# Drone_Basic.net
KiCad netlist of a schematic drawn in EAGLE
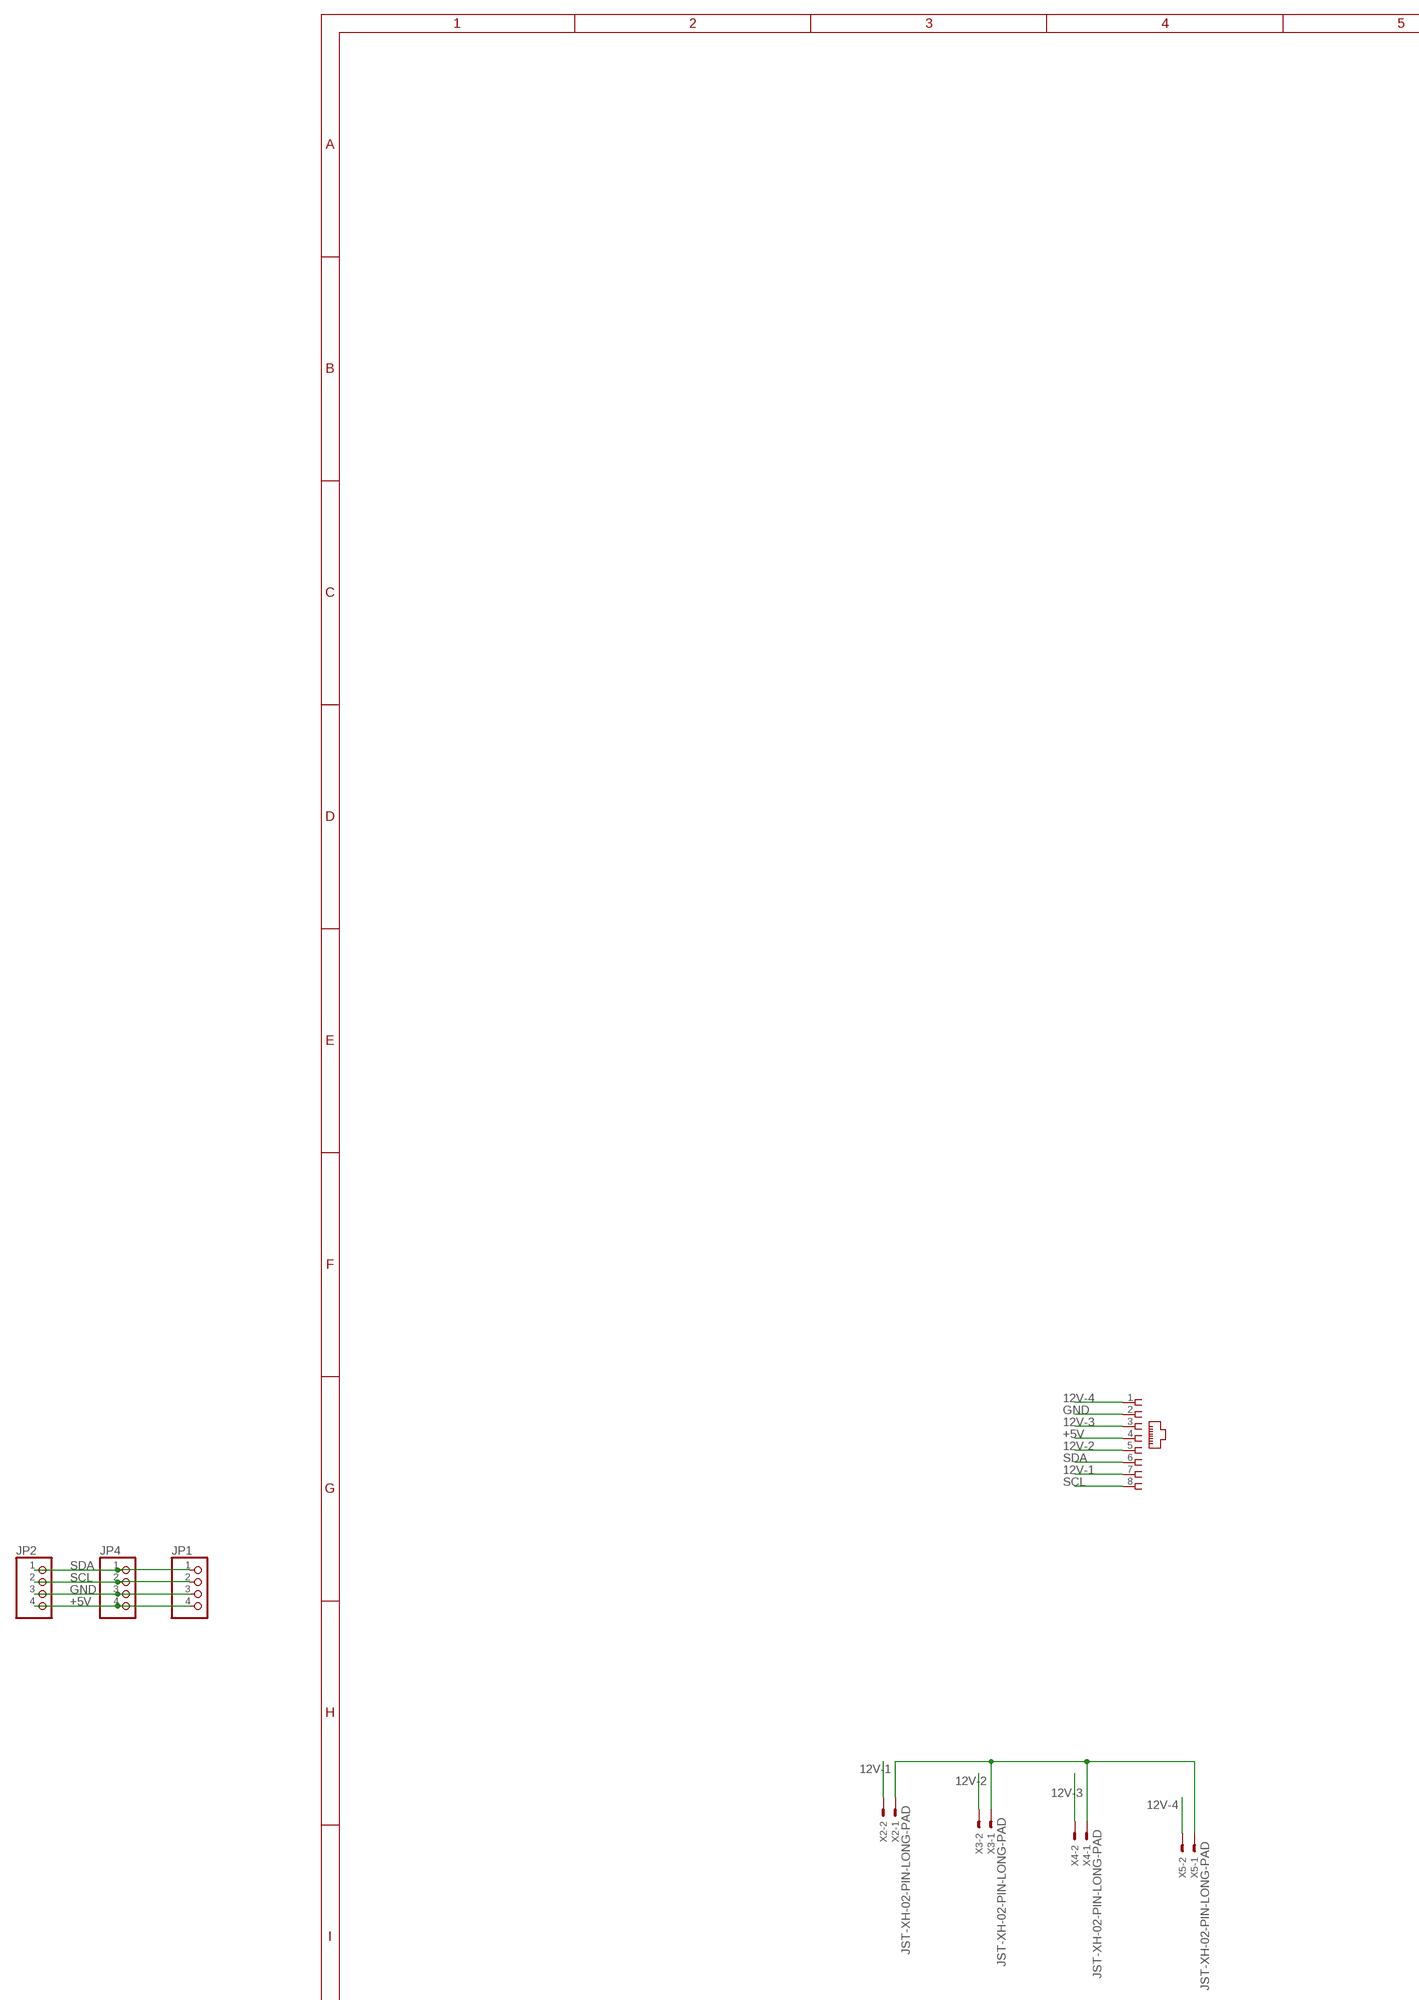
[diagram p0: schematic, sheet 1, part 1 of 2]
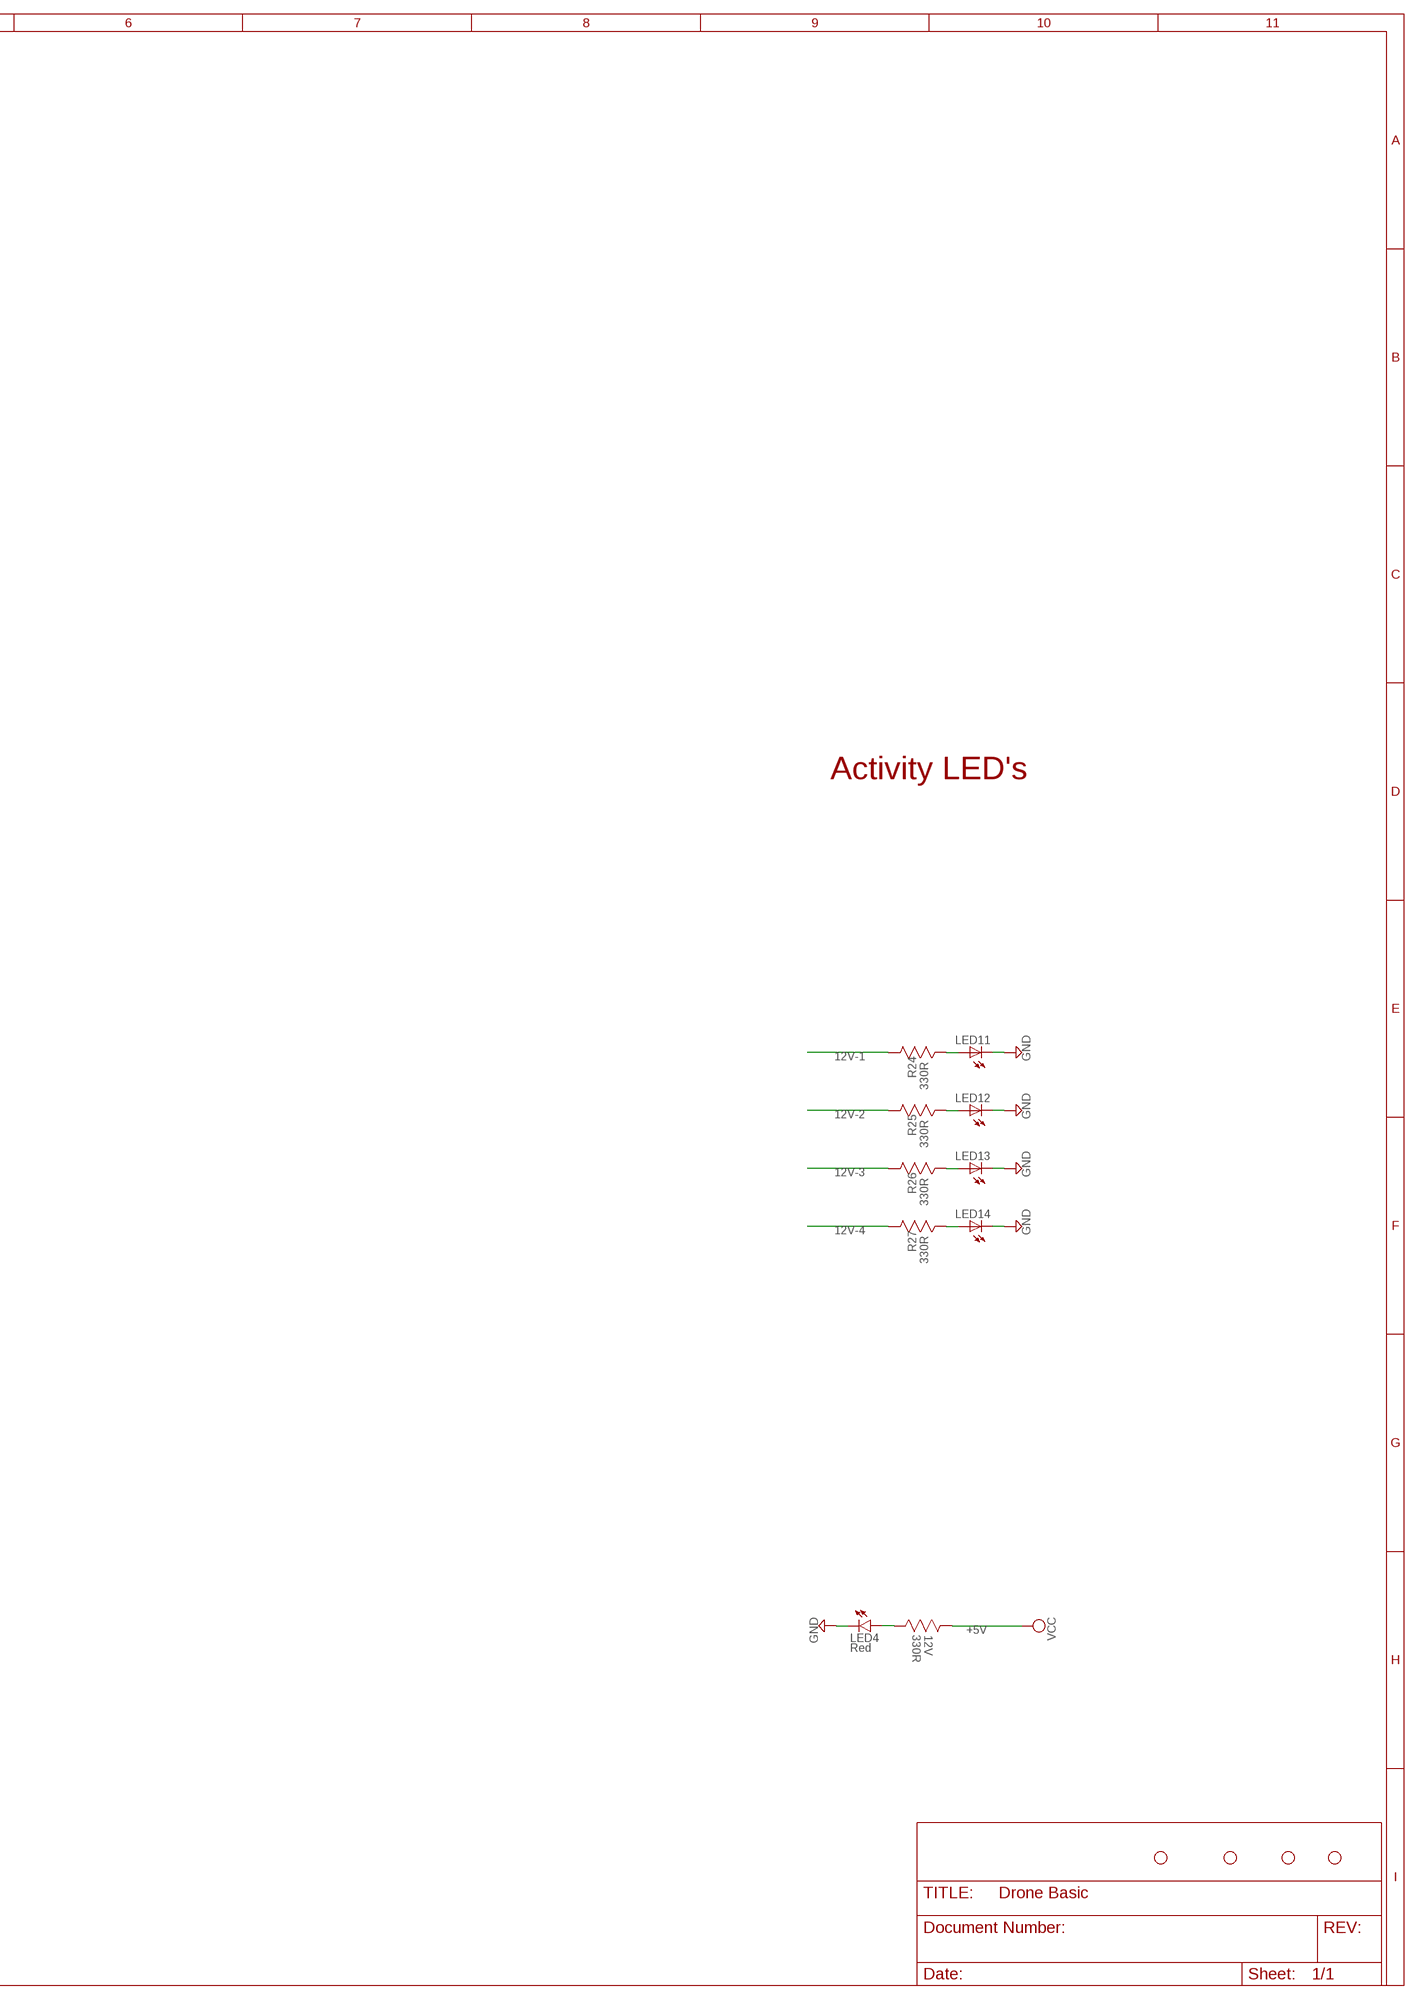
[diagram p1: schematic, sheet 1, part 2 of 2]

(export (version "E")
  (design (tool "Eeschema 10.0.6"))
  (components
    (comp (ref "12V")
      (value "330R")
      (footprint "eagle-import:RESC1608X60N")
      (fields (field (name "MPN") "MC0.063W06031%330R") (field (name "TOLERANCE") "±1%"))
      (libsource (lib "eagle-import") (part "MC0.063W06031%330R"))
    )
    (comp (ref "H5")
      (value "STAND-OFF")
      (footprint "eagle-import:STAND-OFF")
      (libsource (lib "eagle-import") (part "STAND-OFF"))
    )
    (comp (ref "H6")
      (value "STAND-OFF")
      (footprint "eagle-import:STAND-OFF")
      (libsource (lib "eagle-import") (part "STAND-OFF"))
    )
    (comp (ref "H7")
      (value "STAND-OFF")
      (footprint "eagle-import:STAND-OFF")
      (libsource (lib "eagle-import") (part "STAND-OFF"))
    )
    (comp (ref "H8")
      (value "STAND-OFF")
      (footprint "eagle-import:STAND-OFF")
      (libsource (lib "eagle-import") (part "STAND-OFF"))
    )
    (comp (ref "JP1")
      (value "PINHD-1X4")
      (footprint "eagle-import:1X04")
      (libsource (lib "eagle-import") (part "PINHD-1X4"))
    )
    (comp (ref "JP2")
      (value "PINHD-1X4")
      (footprint "eagle-import:1X04")
      (libsource (lib "eagle-import") (part "PINHD-1X4"))
    )
    (comp (ref "JP4")
      (value "PINHD-1X4")
      (footprint "eagle-import:1X04")
      (libsource (lib "eagle-import") (part "PINHD-1X4"))
    )
    (comp (ref "LED4")
      (value "Red")
      (footprint "eagle-import:LED-0603")
      (libsource (lib "eagle-import") (part "LED-RED-0603-WE"))
    )
    (comp (ref "LED11")
      (value "BLUE")
      (footprint "eagle-import:CHIPLED_0805")
      (libsource (lib "eagle-import") (part "LEDCHIPLED_0805"))
    )
    (comp (ref "LED12")
      (value "GREEN")
      (footprint "eagle-import:CHIPLED_0805")
      (libsource (lib "eagle-import") (part "LEDCHIPLED_0805"))
    )
    (comp (ref "LED13")
      (value "Yellow")
      (footprint "eagle-import:CHIPLED_0805")
      (libsource (lib "eagle-import") (part "LEDCHIPLED_0805"))
    )
    (comp (ref "LED14")
      (value "RED")
      (footprint "eagle-import:CHIPLED_0805")
      (libsource (lib "eagle-import") (part "LEDCHIPLED_0805"))
    )
    (comp (ref "PUMPBOX-2")
      (value "RJ45-6L-B")
      (footprint "eagle-import:RJ45-NO-SHIELD")
      (libsource (lib "eagle-import") (part "RJ45-6L-B"))
    )
    (comp (ref "R24")
      (value "330R")
      (footprint "eagle-import:RESC1608X60N")
      (fields (field (name "MPN") "MC0.063W06031%330R") (field (name "TOLERANCE") "±1%"))
      (libsource (lib "eagle-import") (part "MC0.063W06031%330R"))
    )
    (comp (ref "R25")
      (value "330R")
      (footprint "eagle-import:RESC1608X60N")
      (fields (field (name "MPN") "MC0.063W06031%330R") (field (name "TOLERANCE") "±1%"))
      (libsource (lib "eagle-import") (part "MC0.063W06031%330R"))
    )
    (comp (ref "R26")
      (value "330R")
      (footprint "eagle-import:RESC1608X60N")
      (fields (field (name "MPN") "MC0.063W06031%330R") (field (name "TOLERANCE") "±1%"))
      (libsource (lib "eagle-import") (part "MC0.063W06031%330R"))
    )
    (comp (ref "R27")
      (value "330R")
      (footprint "eagle-import:RESC1608X60N")
      (fields (field (name "MPN") "MC0.063W06031%330R") (field (name "TOLERANCE") "±1%"))
      (libsource (lib "eagle-import") (part "MC0.063W06031%330R"))
    )
    (comp (ref "X2")
      (value "JST-XH-02-PIN-LONG-PAD")
      (footprint "eagle-import:JST-XH-02-PACKAGE-LONG-PAD")
      (libsource (lib "eagle-import") (part "JST-XH-02-PIN-LONG-PAD"))
    )
    (comp (ref "X3")
      (value "JST-XH-02-PIN-LONG-PAD")
      (footprint "eagle-import:JST-XH-02-PACKAGE-LONG-PAD")
      (libsource (lib "eagle-import") (part "JST-XH-02-PIN-LONG-PAD"))
    )
    (comp (ref "X4")
      (value "JST-XH-02-PIN-LONG-PAD")
      (footprint "eagle-import:JST-XH-02-PACKAGE-LONG-PAD")
      (libsource (lib "eagle-import") (part "JST-XH-02-PIN-LONG-PAD"))
    )
    (comp (ref "X5")
      (value "JST-XH-02-PIN-LONG-PAD")
      (footprint "eagle-import:JST-XH-02-PACKAGE-LONG-PAD")
      (libsource (lib "eagle-import") (part "JST-XH-02-PIN-LONG-PAD"))
    )
  )
  (nets
    (net (code "1") (name "/12V-1") (class "Default")
      (node (ref "PUMPBOX-2") (pin "7") (pinfunction "7_7") (pintype "passive"))
      (node (ref "R24") (pin "1") (pinfunction "R1_1") (pintype "passive"))
      (node (ref "X2") (pin "2") (pinfunction "S_2") (pintype "passive"))
    )
    (net (code "2") (name "/12V-2") (class "Default")
      (node (ref "PUMPBOX-2") (pin "5") (pinfunction "5_5") (pintype "passive"))
      (node (ref "R25") (pin "1") (pinfunction "R1_1") (pintype "passive"))
      (node (ref "X3") (pin "2") (pinfunction "S_2") (pintype "passive"))
    )
    (net (code "3") (name "/12V-3") (class "Default")
      (node (ref "PUMPBOX-2") (pin "3") (pinfunction "3_3") (pintype "passive"))
      (node (ref "R26") (pin "1") (pinfunction "R1_1") (pintype "passive"))
      (node (ref "X4") (pin "2") (pinfunction "S_2") (pintype "passive"))
    )
    (net (code "4") (name "/12V-4") (class "Default")
      (node (ref "PUMPBOX-2") (pin "1") (pinfunction "1_1") (pintype "passive"))
      (node (ref "R27") (pin "1") (pinfunction "R1_1") (pintype "passive"))
      (node (ref "X5") (pin "2") (pinfunction "S_2") (pintype "passive"))
    )
    (net (code "5") (name "/SCL") (class "Default")
      (node (ref "JP1") (pin "2") (pinfunction "2_2") (pintype "passive"))
      (node (ref "JP2") (pin "2") (pinfunction "2_2") (pintype "passive"))
      (node (ref "JP4") (pin "2") (pinfunction "2_2") (pintype "passive"))
      (node (ref "PUMPBOX-2") (pin "8") (pinfunction "8_8") (pintype "passive"))
    )
    (net (code "6") (name "/SDA") (class "Default")
      (node (ref "JP1") (pin "1") (pinfunction "1_1") (pintype "passive"))
      (node (ref "JP2") (pin "1") (pinfunction "1_1") (pintype "passive"))
      (node (ref "JP4") (pin "1") (pinfunction "1_1") (pintype "passive"))
      (node (ref "PUMPBOX-2") (pin "6") (pinfunction "6_6") (pintype "passive"))
    )
    (net (code "7") (name "GND") (class "Default")
      (node (ref "JP1") (pin "3") (pinfunction "3_3") (pintype "passive"))
      (node (ref "JP2") (pin "3") (pinfunction "3_3") (pintype "passive"))
      (node (ref "JP4") (pin "3") (pinfunction "3_3") (pintype "passive"))
      (node (ref "LED11") (pin "C") (pinfunction "C_C") (pintype "passive"))
      (node (ref "LED12") (pin "C") (pinfunction "C_C") (pintype "passive"))
      (node (ref "LED13") (pin "C") (pinfunction "C_C") (pintype "passive"))
      (node (ref "LED14") (pin "C") (pinfunction "C_C") (pintype "passive"))
      (node (ref "LED4") (pin "C") (pinfunction "C_C") (pintype "passive"))
      (node (ref "PUMPBOX-2") (pin "2") (pinfunction "2_2") (pintype "passive"))
      (node (ref "X2") (pin "1") (pinfunction "S_1") (pintype "passive"))
      (node (ref "X3") (pin "1") (pinfunction "S_1") (pintype "passive"))
      (node (ref "X4") (pin "1") (pinfunction "S_1") (pintype "passive"))
      (node (ref "X5") (pin "1") (pinfunction "S_1") (pintype "passive"))
    )
    (net (code "8") (name "Net-(12V-R2)") (class "Default")
      (node (ref "12V") (pin "2") (pinfunction "R2_2") (pintype "passive"))
      (node (ref "LED4") (pin "A") (pinfunction "A_A") (pintype "passive"))
    )
    (net (code "9") (name "Net-(R24-R2)") (class "Default")
      (node (ref "LED11") (pin "A") (pinfunction "A_A") (pintype "passive"))
      (node (ref "R24") (pin "2") (pinfunction "R2_2") (pintype "passive"))
    )
    (net (code "10") (name "Net-(R25-R2)") (class "Default")
      (node (ref "LED12") (pin "A") (pinfunction "A_A") (pintype "passive"))
      (node (ref "R25") (pin "2") (pinfunction "R2_2") (pintype "passive"))
    )
    (net (code "11") (name "Net-(R26-R2)") (class "Default")
      (node (ref "LED13") (pin "A") (pinfunction "A_A") (pintype "passive"))
      (node (ref "R26") (pin "2") (pinfunction "R2_2") (pintype "passive"))
    )
    (net (code "12") (name "Net-(R27-R2)") (class "Default")
      (node (ref "LED14") (pin "A") (pinfunction "A_A") (pintype "passive"))
      (node (ref "R27") (pin "2") (pinfunction "R2_2") (pintype "passive"))
    )
    (net (code "13") (name "VCC") (class "Default")
      (node (ref "12V") (pin "1") (pinfunction "R1_1") (pintype "passive"))
      (node (ref "JP1") (pin "4") (pinfunction "4_4") (pintype "passive"))
      (node (ref "JP2") (pin "4") (pinfunction "4_4") (pintype "passive"))
      (node (ref "JP4") (pin "4") (pinfunction "4_4") (pintype "passive"))
      (node (ref "PUMPBOX-2") (pin "4") (pinfunction "4_4") (pintype "passive"))
    )
  )
)
